# 4G.net
KiCad netlist of a schematic drawn in Altium Designer
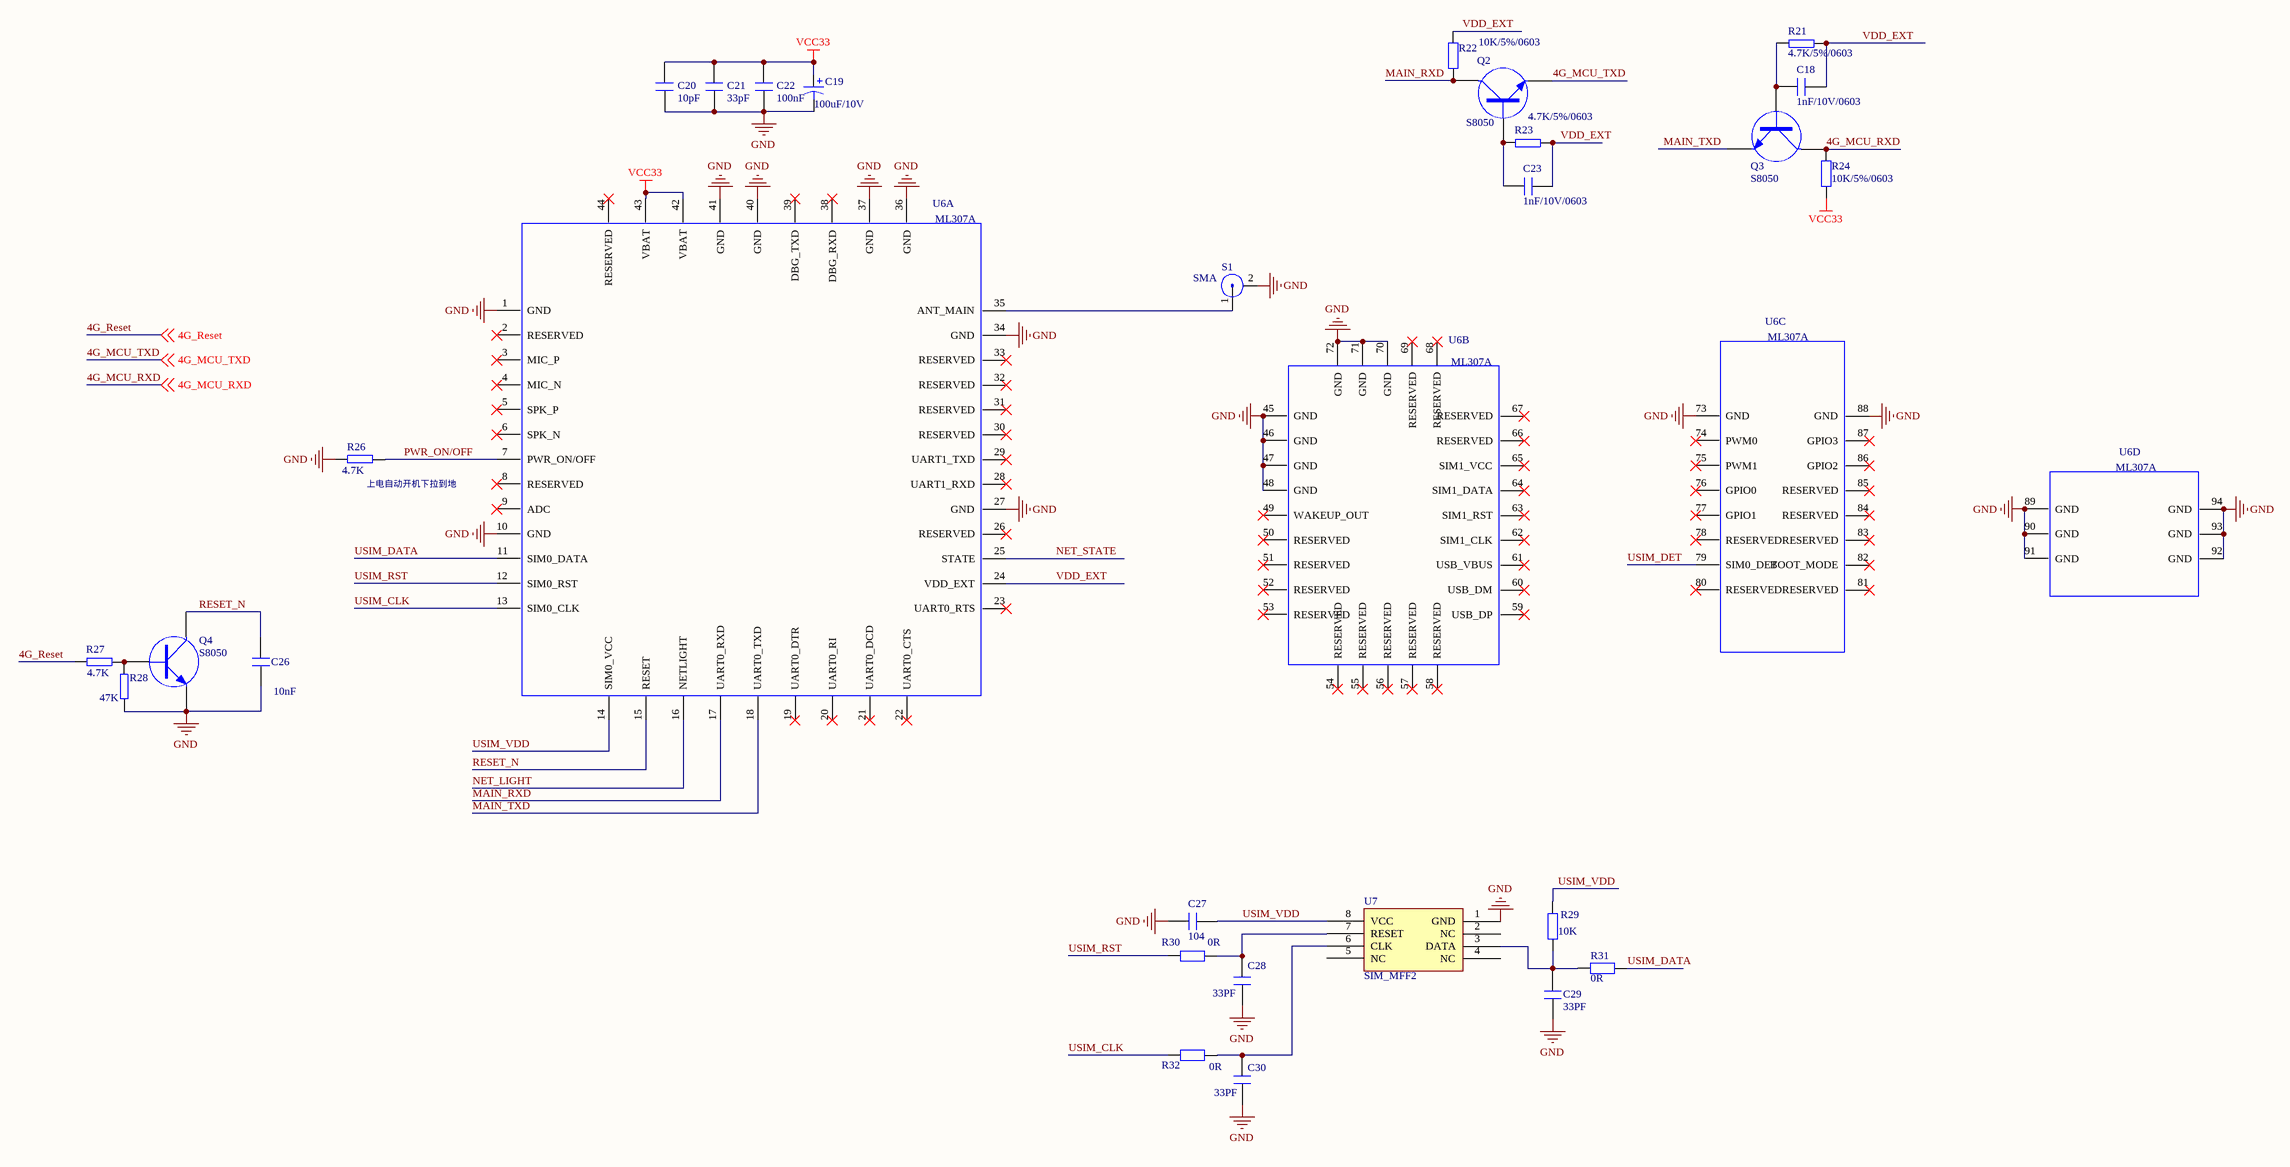
[diagram p0: 4G.SchDoc]

(export (version "E")
  (design (tool "Eeschema 10.0.6"))
  (components
    (comp (ref "C18")
      (value "1nF/10V/0603")
      (footprint "0603R")
      (libsource (lib "ES_Schematic") (part "CAP"))
    )
    (comp (ref "C19")
      (value "100uF/10V")
      (footprint "C1210")
      (description "Polarized Capacitor (Radial)")
      (fields (field (name "PUBLISHER") "Altium Limited"))
      (libsource (lib "Miscellaneous Devices") (part "Cap Pol1"))
    )
    (comp (ref "C20") (value "10pF") (footprint "0603R") (libsource (lib "ES_Schematic") (part "CAP_1")))
    (comp (ref "C21") (value "33pF") (footprint "0603R") (libsource (lib "ES_Schematic") (part "CAP_1")))
    (comp (ref "C22") (value "100nF") (footprint "0603R") (libsource (lib "ES_Schematic") (part "CAP_1")))
    (comp (ref "C23")
      (value "1nF/10V/0603")
      (footprint "0603R")
      (libsource (lib "ES_Schematic") (part "CAP"))
    )
    (comp (ref "C26") (value "10nF") (footprint "0603R") (libsource (lib "ES_Schematic") (part "CAP_1")))
    (comp (ref "C27") (value "104") (footprint "0603R") (libsource (lib "ES_Schematic") (part "CAP")))
    (comp (ref "C28") (value "33PF") (footprint "0603R") (libsource (lib "ES_Schematic") (part "CAP")))
    (comp (ref "C29") (value "33PF") (footprint "0603R") (libsource (lib "ES_Schematic") (part "CAP")))
    (comp (ref "C30") (value "33PF") (footprint "0603R") (libsource (lib "ES_Schematic") (part "CAP")))
    (comp (ref "Q2") (value "S8050") (footprint "SOT-23") (libsource (lib "ES_Schematic") (part "NPN")))
    (comp (ref "Q3") (value "S8050") (footprint "SOT-23") (libsource (lib "ES_Schematic") (part "NPN")))
    (comp (ref "Q4") (value "S8050") (footprint "SOT-23") (libsource (lib "ES_Schematic") (part "NPN")))
    (comp (ref "R21")
      (value "4.7K/5%/0603")
      (footprint "0603R")
      (libsource (lib "ES_Schematic") (part "RES"))
    )
    (comp (ref "R22")
      (value "10K/5%/0603")
      (footprint "0603R")
      (description "Resistor")
      (fields (field (name "PUBLISHER") "Altium Limited"))
      (libsource (lib "Miscellaneous Devices") (part "Res2"))
    )
    (comp (ref "R23")
      (value "4.7K/5%/0603")
      (footprint "0603R")
      (libsource (lib "ES_Schematic") (part "RES"))
    )
    (comp (ref "R24")
      (value "10K/5%/0603")
      (footprint "0603R")
      (description "Resistor")
      (fields (field (name "PUBLISHER") "Altium Limited"))
      (libsource (lib "Miscellaneous Devices") (part "Res2"))
    )
    (comp (ref "R26") (value "4.7K") (footprint "0603R") (libsource (lib "ES_Schematic") (part "RES")))
    (comp (ref "R27") (value "4.7K") (footprint "0603R") (libsource (lib "ES_Schematic") (part "RES")))
    (comp (ref "R28") (value "47K") (footprint "0603R") (libsource (lib "ES_Schematic") (part "RES")))
    (comp (ref "R29")
      (value "10K")
      (footprint "0603R")
      (description "Resistor")
      (fields (field (name "PUBLISHER") "Altium Limited"))
      (libsource (lib "Miscellaneous Devices") (part "Res2"))
    )
    (comp (ref "R30")
      (value "0R")
      (footprint "0603R")
      (description "Resistor")
      (fields (field (name "PUBLISHER") "Altium Limited"))
      (libsource (lib "") (part "Res2_1"))
    )
    (comp (ref "R31")
      (value "0R")
      (footprint "0603R")
      (description "Resistor")
      (fields (field (name "PUBLISHER") "Altium Limited"))
      (libsource (lib "") (part "Res2_1"))
    )
    (comp (ref "R32")
      (value "0R")
      (footprint "0603R")
      (description "Resistor")
      (fields (field (name "PUBLISHER") "Altium Limited"))
      (libsource (lib "") (part "Res2_1"))
    )
    (comp (ref "S1") (value "SMA") (footprint "RF1-00283天线座") (libsource (lib "ES_Schematic") (part "SMA")))
    (comp (ref "U6") (value "ML307A") (footprint "ML307A") (libsource (lib "") (part "ML307A_1")))
    (comp (ref "U7")
      (value "SIM_MFF2")
      (footprint "VQFN8")
      (libsource (lib "ES_Schematic") (part "SIM_MFF2"))
    )
  )
  (nets
    (net (code "1") (name "/MAIN_RXD") (class "Default")
      (node (ref "Q2") (pin "3") (pinfunction "C_3") (pintype "passive"))
      (node (ref "R22") (pin "2") (pinfunction "2_2") (pintype "passive"))
      (node (ref "U6") (pin "17") (pinfunction "UART0_RXD_17") (pintype "passive"))
    )
    (net (code "2") (name "/MAIN_TXD") (class "Default")
      (node (ref "Q3") (pin "2") (pinfunction "E_2") (pintype "passive"))
      (node (ref "U6") (pin "18") (pinfunction "UART0_TXD_18") (pintype "passive"))
    )
    (net (code "3") (name "/NET_LIGHT") (class "Default")
      (node (ref "U6") (pin "16") (pinfunction "NETLIGHT_16") (pintype "passive"))
    )
    (net (code "4") (name "/NET_STATE") (class "Default")
      (node (ref "U6") (pin "25") (pinfunction "STATE_25") (pintype "passive"))
    )
    (net (code "5") (name "/PWR_ON{slash}OFF") (class "Default")
      (node (ref "R26") (pin "1") (pinfunction "1_1") (pintype "passive"))
      (node (ref "U6") (pin "7") (pinfunction "PWR_ON/OFF_7") (pintype "passive"))
    )
    (net (code "6") (name "/RESET_N") (class "Default")
      (node (ref "C26") (pin "2") (pinfunction "2_2") (pintype "passive"))
      (node (ref "Q4") (pin "3") (pinfunction "C_3") (pintype "passive"))
      (node (ref "U6") (pin "15") (pinfunction "RESET_15") (pintype "passive"))
    )
    (net (code "7") (name "/USIM_CLK") (class "Default")
      (node (ref "R32") (pin "2") (pinfunction "2_2") (pintype "passive"))
      (node (ref "U6") (pin "13") (pinfunction "SIM0_CLK_13") (pintype "passive"))
    )
    (net (code "8") (name "/USIM_DATA") (class "Default")
      (node (ref "R31") (pin "1") (pinfunction "1_1") (pintype "passive"))
      (node (ref "U6") (pin "11") (pinfunction "SIM0_DATA_11") (pintype "passive"))
    )
    (net (code "9") (name "/USIM_DET") (class "Default")
      (node (ref "U6") (pin "79") (pinfunction "SIM0_DET_79") (pintype "passive"))
    )
    (net (code "10") (name "/USIM_RST") (class "Default")
      (node (ref "R30") (pin "2") (pinfunction "2_2") (pintype "passive"))
      (node (ref "U6") (pin "12") (pinfunction "SIM0_RST_12") (pintype "passive"))
    )
    (net (code "11") (name "/USIM_VDD") (class "Default")
      (node (ref "C27") (pin "2") (pinfunction "2_2") (pintype "passive"))
      (node (ref "R29") (pin "1") (pinfunction "1_1") (pintype "passive"))
      (node (ref "U6") (pin "14") (pinfunction "SIM0_VCC_14") (pintype "passive"))
      (node (ref "U7") (pin "8") (pinfunction "VCC_8") (pintype "passive"))
    )
    (net (code "12") (name "/VDD_EXT") (class "Default")
      (node (ref "C18") (pin "2") (pinfunction "2_2") (pintype "passive"))
      (node (ref "C23") (pin "2") (pinfunction "2_2") (pintype "passive"))
      (node (ref "R21") (pin "2") (pinfunction "2_2") (pintype "passive"))
      (node (ref "R22") (pin "1") (pinfunction "1_1") (pintype "passive"))
      (node (ref "R23") (pin "2") (pinfunction "2_2") (pintype "passive"))
      (node (ref "U6") (pin "24") (pinfunction "VDD_EXT_24") (pintype "passive"))
    )
    (net (code "13") (name "4G_MCU_RXD") (class "Default")
      (node (ref "Q3") (pin "3") (pinfunction "C_3") (pintype "passive"))
      (node (ref "R24") (pin "1") (pinfunction "1_1") (pintype "passive"))
    )
    (net (code "14") (name "4G_MCU_TXD") (class "Default")
      (node (ref "Q2") (pin "2") (pinfunction "E_2") (pintype "passive"))
    )
    (net (code "15") (name "4G_Reset") (class "Default")
      (node (ref "R27") (pin "1") (pinfunction "1_1") (pintype "passive"))
    )
    (net (code "16") (name "GND") (class "Default")
      (node (ref "C19") (pin "2") (pinfunction "2_2") (pintype "passive"))
      (node (ref "C20") (pin "2") (pinfunction "2_2") (pintype "passive"))
      (node (ref "C21") (pin "2") (pinfunction "2_2") (pintype "passive"))
      (node (ref "C22") (pin "2") (pinfunction "2_2") (pintype "passive"))
      (node (ref "C26") (pin "1") (pinfunction "1_1") (pintype "passive"))
      (node (ref "C27") (pin "1") (pinfunction "1_1") (pintype "passive"))
      (node (ref "C28") (pin "2") (pinfunction "2_2") (pintype "passive"))
      (node (ref "C29") (pin "1") (pinfunction "1_1") (pintype "passive"))
      (node (ref "C30") (pin "2") (pinfunction "2_2") (pintype "passive"))
      (node (ref "Q4") (pin "2") (pinfunction "E_2") (pintype "passive"))
      (node (ref "R26") (pin "2") (pinfunction "2_2") (pintype "passive"))
      (node (ref "R28") (pin "2") (pinfunction "2_2") (pintype "passive"))
      (node (ref "S1") (pin "2") (pinfunction "2_2") (pintype "passive"))
      (node (ref "U6") (pin "1") (pinfunction "GND_1") (pintype "passive"))
      (node (ref "U6") (pin "10") (pinfunction "GND_10") (pintype "passive"))
      (node (ref "U6") (pin "27") (pinfunction "GND_27") (pintype "passive"))
      (node (ref "U6") (pin "34") (pinfunction "GND_34") (pintype "passive"))
      (node (ref "U6") (pin "36") (pinfunction "GND_36") (pintype "passive"))
      (node (ref "U6") (pin "37") (pinfunction "GND_37") (pintype "passive"))
      (node (ref "U6") (pin "40") (pinfunction "GND_40") (pintype "passive"))
      (node (ref "U6") (pin "41") (pinfunction "GND_41") (pintype "passive"))
      (node (ref "U6") (pin "45") (pinfunction "GND_45") (pintype "passive"))
      (node (ref "U6") (pin "46") (pinfunction "GND_46") (pintype "passive"))
      (node (ref "U6") (pin "47") (pinfunction "GND_47") (pintype "passive"))
      (node (ref "U6") (pin "48") (pinfunction "GND_48") (pintype "passive"))
      (node (ref "U6") (pin "70") (pinfunction "GND_70") (pintype "passive"))
      (node (ref "U6") (pin "71") (pinfunction "GND_71") (pintype "passive"))
      (node (ref "U6") (pin "72") (pinfunction "GND_72") (pintype "passive"))
      (node (ref "U6") (pin "73") (pinfunction "GND_73") (pintype "passive"))
      (node (ref "U6") (pin "88") (pinfunction "GND_88") (pintype "passive"))
      (node (ref "U6") (pin "89") (pinfunction "GND_89") (pintype "passive"))
      (node (ref "U6") (pin "90") (pinfunction "GND_90") (pintype "passive"))
      (node (ref "U6") (pin "91") (pinfunction "GND_91") (pintype "passive"))
      (node (ref "U6") (pin "92") (pinfunction "GND_92") (pintype "passive"))
      (node (ref "U6") (pin "93") (pinfunction "GND_93") (pintype "passive"))
      (node (ref "U6") (pin "94") (pinfunction "GND_94") (pintype "passive"))
      (node (ref "U7") (pin "1") (pinfunction "GND_1") (pintype "passive"))
    )
    (net (code "17") (name "Net-(Q2-B)") (class "Default")
      (node (ref "C23") (pin "1") (pinfunction "1_1") (pintype "passive"))
      (node (ref "Q2") (pin "1") (pinfunction "B_1") (pintype "passive"))
      (node (ref "R23") (pin "1") (pinfunction "1_1") (pintype "passive"))
    )
    (net (code "18") (name "Net-(Q3-B)") (class "Default")
      (node (ref "C18") (pin "1") (pinfunction "1_1") (pintype "passive"))
      (node (ref "Q3") (pin "1") (pinfunction "B_1") (pintype "passive"))
      (node (ref "R21") (pin "1") (pinfunction "1_1") (pintype "passive"))
    )
    (net (code "19") (name "Net-(Q4-B)") (class "Default")
      (node (ref "Q4") (pin "1") (pinfunction "B_1") (pintype "passive"))
      (node (ref "R27") (pin "2") (pinfunction "2_2") (pintype "passive"))
      (node (ref "R28") (pin "1") (pinfunction "1_1") (pintype "passive"))
    )
    (net (code "20") (name "Net-(U6A-ANT_MAIN)") (class "Default")
      (node (ref "S1") (pin "1") (pinfunction "1_1") (pintype "passive"))
      (node (ref "U6") (pin "35") (pinfunction "ANT_MAIN_35") (pintype "passive"))
    )
    (net (code "21") (name "Net-(U7-CLK)") (class "Default")
      (node (ref "C30") (pin "1") (pinfunction "1_1") (pintype "passive"))
      (node (ref "R32") (pin "1") (pinfunction "1_1") (pintype "passive"))
      (node (ref "U7") (pin "6") (pinfunction "CLK_6") (pintype "passive"))
    )
    (net (code "22") (name "Net-(U7-DATA)") (class "Default")
      (node (ref "C29") (pin "2") (pinfunction "2_2") (pintype "passive"))
      (node (ref "R29") (pin "2") (pinfunction "2_2") (pintype "passive"))
      (node (ref "R31") (pin "2") (pinfunction "2_2") (pintype "passive"))
      (node (ref "U7") (pin "3") (pinfunction "DATA_3") (pintype "passive"))
    )
    (net (code "23") (name "Net-(U7-RESET)") (class "Default")
      (node (ref "C28") (pin "1") (pinfunction "1_1") (pintype "passive"))
      (node (ref "R30") (pin "1") (pinfunction "1_1") (pintype "passive"))
      (node (ref "U7") (pin "7") (pinfunction "RESET_7") (pintype "passive"))
    )
    (net (code "24") (name "VCC33") (class "Default")
      (node (ref "C19") (pin "1") (pinfunction "1_1") (pintype "passive"))
      (node (ref "C20") (pin "1") (pinfunction "1_1") (pintype "passive"))
      (node (ref "C21") (pin "1") (pinfunction "1_1") (pintype "passive"))
      (node (ref "C22") (pin "1") (pinfunction "1_1") (pintype "passive"))
      (node (ref "R24") (pin "2") (pinfunction "2_2") (pintype "passive"))
      (node (ref "U6") (pin "42") (pinfunction "VBAT_42") (pintype "passive"))
      (node (ref "U6") (pin "43") (pinfunction "VBAT_43") (pintype "passive"))
    )
    (net (code "25") (name "unconnected-(U6A-ADC-Pad9)") (class "Default")
      (node (ref "U6") (pin "9") (pinfunction "ADC_9") (pintype "passive+no_connect"))
    )
    (net (code "26") (name "unconnected-(U6A-DBG_RXD-Pad38)") (class "Default")
      (node (ref "U6") (pin "38") (pinfunction "DBG_RXD_38") (pintype "passive+no_connect"))
    )
    (net (code "27") (name "unconnected-(U6A-DBG_TXD-Pad39)") (class "Default")
      (node (ref "U6") (pin "39") (pinfunction "DBG_TXD_39") (pintype "passive+no_connect"))
    )
    (net (code "28") (name "unconnected-(U6A-MIC_N-Pad4)") (class "Default")
      (node (ref "U6") (pin "4") (pinfunction "MIC_N_4") (pintype "passive+no_connect"))
    )
    (net (code "29") (name "unconnected-(U6A-MIC_P-Pad3)") (class "Default")
      (node (ref "U6") (pin "3") (pinfunction "MIC_P_3") (pintype "passive+no_connect"))
    )
    (net (code "30") (name "unconnected-(U6A-RESERVED-Pad2)") (class "Default")
      (node (ref "U6") (pin "2") (pinfunction "RESERVED_2") (pintype "passive+no_connect"))
    )
    (net (code "31") (name "unconnected-(U6A-RESERVED-Pad8)") (class "Default")
      (node (ref "U6") (pin "8") (pinfunction "RESERVED_8") (pintype "passive+no_connect"))
    )
    (net (code "32") (name "unconnected-(U6A-RESERVED-Pad26)") (class "Default")
      (node (ref "U6") (pin "26") (pinfunction "RESERVED_26") (pintype "passive+no_connect"))
    )
    (net (code "33") (name "unconnected-(U6A-RESERVED-Pad30)") (class "Default")
      (node (ref "U6") (pin "30") (pinfunction "RESERVED_30") (pintype "passive+no_connect"))
    )
    (net (code "34") (name "unconnected-(U6A-RESERVED-Pad31)") (class "Default")
      (node (ref "U6") (pin "31") (pinfunction "RESERVED_31") (pintype "passive+no_connect"))
    )
    (net (code "35") (name "unconnected-(U6A-RESERVED-Pad32)") (class "Default")
      (node (ref "U6") (pin "32") (pinfunction "RESERVED_32") (pintype "passive+no_connect"))
    )
    (net (code "36") (name "unconnected-(U6A-RESERVED-Pad33)") (class "Default")
      (node (ref "U6") (pin "33") (pinfunction "RESERVED_33") (pintype "passive+no_connect"))
    )
    (net (code "37") (name "unconnected-(U6A-RESERVED-Pad44)") (class "Default")
      (node (ref "U6") (pin "44") (pinfunction "RESERVED_44") (pintype "passive+no_connect"))
    )
    (net (code "38") (name "unconnected-(U6A-SPK_N-Pad6)") (class "Default")
      (node (ref "U6") (pin "6") (pinfunction "SPK_N_6") (pintype "passive+no_connect"))
    )
    (net (code "39") (name "unconnected-(U6A-SPK_P-Pad5)") (class "Default")
      (node (ref "U6") (pin "5") (pinfunction "SPK_P_5") (pintype "passive+no_connect"))
    )
    (net (code "40") (name "unconnected-(U6A-UART0_CTS-Pad22)") (class "Default")
      (node (ref "U6") (pin "22") (pinfunction "UART0_CTS_22") (pintype "passive+no_connect"))
    )
    (net (code "41") (name "unconnected-(U6A-UART0_DCD-Pad21)") (class "Default")
      (node (ref "U6") (pin "21") (pinfunction "UART0_DCD_21") (pintype "passive+no_connect"))
    )
    (net (code "42") (name "unconnected-(U6A-UART0_DTR-Pad19)") (class "Default")
      (node (ref "U6") (pin "19") (pinfunction "UART0_DTR_19") (pintype "passive+no_connect"))
    )
    (net (code "43") (name "unconnected-(U6A-UART0_RI-Pad20)") (class "Default")
      (node (ref "U6") (pin "20") (pinfunction "UART0_RI_20") (pintype "passive+no_connect"))
    )
    (net (code "44") (name "unconnected-(U6A-UART0_RTS-Pad23)") (class "Default")
      (node (ref "U6") (pin "23") (pinfunction "UART0_RTS_23") (pintype "passive+no_connect"))
    )
    (net (code "45") (name "unconnected-(U6A-UART1_RXD-Pad28)") (class "Default")
      (node (ref "U6") (pin "28") (pinfunction "UART1_RXD_28") (pintype "passive+no_connect"))
    )
    (net (code "46") (name "unconnected-(U6A-UART1_TXD-Pad29)") (class "Default")
      (node (ref "U6") (pin "29") (pinfunction "UART1_TXD_29") (pintype "passive+no_connect"))
    )
    (net (code "47") (name "unconnected-(U6B-RESERVED-Pad50)") (class "Default")
      (node (ref "U6") (pin "50") (pinfunction "RESERVED_50") (pintype "passive+no_connect"))
    )
    (net (code "48") (name "unconnected-(U6B-RESERVED-Pad51)") (class "Default")
      (node (ref "U6") (pin "51") (pinfunction "RESERVED_51") (pintype "passive+no_connect"))
    )
    (net (code "49") (name "unconnected-(U6B-RESERVED-Pad52)") (class "Default")
      (node (ref "U6") (pin "52") (pinfunction "RESERVED_52") (pintype "passive+no_connect"))
    )
    (net (code "50") (name "unconnected-(U6B-RESERVED-Pad53)") (class "Default")
      (node (ref "U6") (pin "53") (pinfunction "RESERVED_53") (pintype "passive+no_connect"))
    )
    (net (code "51") (name "unconnected-(U6B-RESERVED-Pad54)") (class "Default")
      (node (ref "U6") (pin "54") (pinfunction "RESERVED_54") (pintype "passive+no_connect"))
    )
    (net (code "52") (name "unconnected-(U6B-RESERVED-Pad55)") (class "Default")
      (node (ref "U6") (pin "55") (pinfunction "RESERVED_55") (pintype "passive+no_connect"))
    )
    (net (code "53") (name "unconnected-(U6B-RESERVED-Pad56)") (class "Default")
      (node (ref "U6") (pin "56") (pinfunction "RESERVED_56") (pintype "passive+no_connect"))
    )
    (net (code "54") (name "unconnected-(U6B-RESERVED-Pad57)") (class "Default")
      (node (ref "U6") (pin "57") (pinfunction "RESERVED_57") (pintype "passive+no_connect"))
    )
    (net (code "55") (name "unconnected-(U6B-RESERVED-Pad58)") (class "Default")
      (node (ref "U6") (pin "58") (pinfunction "RESERVED_58") (pintype "passive+no_connect"))
    )
    (net (code "56") (name "unconnected-(U6B-RESERVED-Pad66)") (class "Default")
      (node (ref "U6") (pin "66") (pinfunction "RESERVED_66") (pintype "passive+no_connect"))
    )
    (net (code "57") (name "unconnected-(U6B-RESERVED-Pad67)") (class "Default")
      (node (ref "U6") (pin "67") (pinfunction "RESERVED_67") (pintype "passive+no_connect"))
    )
    (net (code "58") (name "unconnected-(U6B-RESERVED-Pad68)") (class "Default")
      (node (ref "U6") (pin "68") (pinfunction "RESERVED_68") (pintype "passive+no_connect"))
    )
    (net (code "59") (name "unconnected-(U6B-RESERVED-Pad69)") (class "Default")
      (node (ref "U6") (pin "69") (pinfunction "RESERVED_69") (pintype "passive+no_connect"))
    )
    (net (code "60") (name "unconnected-(U6B-SIM1_CLK-Pad62)") (class "Default")
      (node (ref "U6") (pin "62") (pinfunction "SIM1_CLK_62") (pintype "passive+no_connect"))
    )
    (net (code "61") (name "unconnected-(U6B-SIM1_DATA-Pad64)") (class "Default")
      (node (ref "U6") (pin "64") (pinfunction "SIM1_DATA_64") (pintype "passive+no_connect"))
    )
    (net (code "62") (name "unconnected-(U6B-SIM1_RST-Pad63)") (class "Default")
      (node (ref "U6") (pin "63") (pinfunction "SIM1_RST_63") (pintype "passive+no_connect"))
    )
    (net (code "63") (name "unconnected-(U6B-SIM1_VCC-Pad65)") (class "Default")
      (node (ref "U6") (pin "65") (pinfunction "SIM1_VCC_65") (pintype "passive+no_connect"))
    )
    (net (code "64") (name "unconnected-(U6B-USB_DM-Pad60)") (class "Default")
      (node (ref "U6") (pin "60") (pinfunction "USB_DM_60") (pintype "passive+no_connect"))
    )
    (net (code "65") (name "unconnected-(U6B-USB_DP-Pad59)") (class "Default")
      (node (ref "U6") (pin "59") (pinfunction "USB_DP_59") (pintype "passive+no_connect"))
    )
    (net (code "66") (name "unconnected-(U6B-USB_VBUS-Pad61)") (class "Default")
      (node (ref "U6") (pin "61") (pinfunction "USB_VBUS_61") (pintype "passive+no_connect"))
    )
    (net (code "67") (name "unconnected-(U6B-WAKEUP_OUT-Pad49)") (class "Default")
      (node (ref "U6") (pin "49") (pinfunction "WAKEUP_OUT_49") (pintype "passive+no_connect"))
    )
    (net (code "68") (name "unconnected-(U6C-BOOT_MODE-Pad82)") (class "Default")
      (node (ref "U6") (pin "82") (pinfunction "BOOT_MODE_82") (pintype "passive+no_connect"))
    )
    (net (code "69") (name "unconnected-(U6C-GPIO0-Pad76)") (class "Default")
      (node (ref "U6") (pin "76") (pinfunction "GPIO0_76") (pintype "passive+no_connect"))
    )
    (net (code "70") (name "unconnected-(U6C-GPIO1-Pad77)") (class "Default")
      (node (ref "U6") (pin "77") (pinfunction "GPIO1_77") (pintype "passive+no_connect"))
    )
    (net (code "71") (name "unconnected-(U6C-GPIO2-Pad86)") (class "Default")
      (node (ref "U6") (pin "86") (pinfunction "GPIO2_86") (pintype "passive+no_connect"))
    )
    (net (code "72") (name "unconnected-(U6C-GPIO3-Pad87)") (class "Default")
      (node (ref "U6") (pin "87") (pinfunction "GPIO3_87") (pintype "passive+no_connect"))
    )
    (net (code "73") (name "unconnected-(U6C-PWM0-Pad74)") (class "Default")
      (node (ref "U6") (pin "74") (pinfunction "PWM0_74") (pintype "passive+no_connect"))
    )
    (net (code "74") (name "unconnected-(U6C-PWM1-Pad75)") (class "Default")
      (node (ref "U6") (pin "75") (pinfunction "PWM1_75") (pintype "passive+no_connect"))
    )
    (net (code "75") (name "unconnected-(U6C-RESERVED-Pad78)") (class "Default")
      (node (ref "U6") (pin "78") (pinfunction "RESERVED_78") (pintype "passive+no_connect"))
    )
    (net (code "76") (name "unconnected-(U6C-RESERVED-Pad80)") (class "Default")
      (node (ref "U6") (pin "80") (pinfunction "RESERVED_80") (pintype "passive+no_connect"))
    )
    (net (code "77") (name "unconnected-(U6C-RESERVED-Pad81)") (class "Default")
      (node (ref "U6") (pin "81") (pinfunction "RESERVED_81") (pintype "passive+no_connect"))
    )
    (net (code "78") (name "unconnected-(U6C-RESERVED-Pad83)") (class "Default")
      (node (ref "U6") (pin "83") (pinfunction "RESERVED_83") (pintype "passive+no_connect"))
    )
    (net (code "79") (name "unconnected-(U6C-RESERVED-Pad84)") (class "Default")
      (node (ref "U6") (pin "84") (pinfunction "RESERVED_84") (pintype "passive+no_connect"))
    )
    (net (code "80") (name "unconnected-(U6C-RESERVED-Pad85)") (class "Default")
      (node (ref "U6") (pin "85") (pinfunction "RESERVED_85") (pintype "passive+no_connect"))
    )
    (net (code "81") (name "unconnected-(U7-NC-Pad2)") (class "Default")
      (node (ref "U7") (pin "2") (pinfunction "NC_2") (pintype "passive"))
    )
    (net (code "82") (name "unconnected-(U7-NC-Pad4)") (class "Default")
      (node (ref "U7") (pin "4") (pinfunction "NC_4") (pintype "passive"))
    )
    (net (code "83") (name "unconnected-(U7-NC-Pad5)") (class "Default")
      (node (ref "U7") (pin "5") (pinfunction "NC_5") (pintype "passive"))
    )
  )
)
